# eagle_schematic.net
KiCad netlist of a schematic drawn in EAGLE
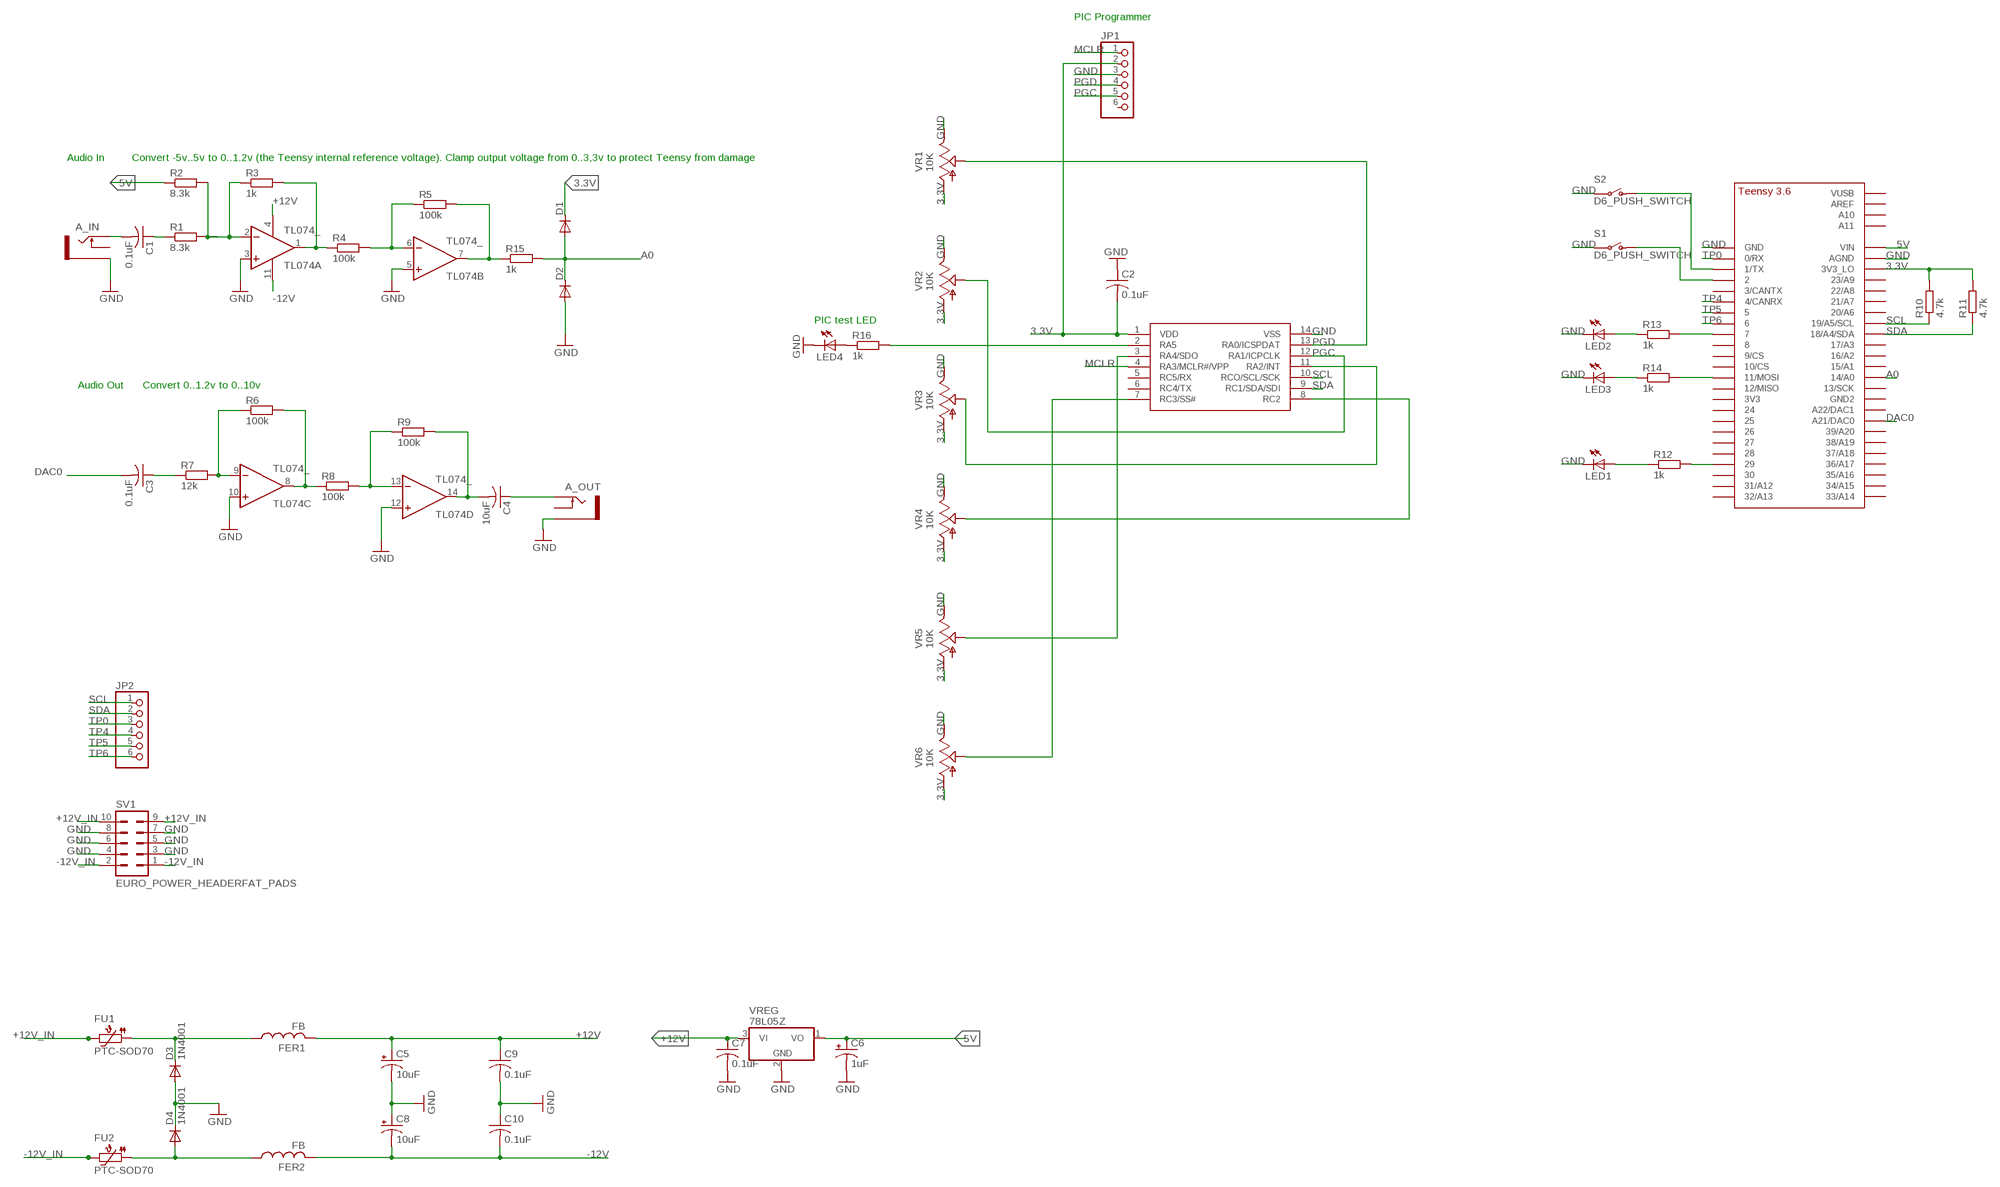
[diagram p0: schematic, sheet 1]

(export (version "E")
  (design (tool "Eeschema 10.0.6"))
  (components
    (comp (ref "A_IN")
      (value "THONKICONNNEW")
      (footprint "eagle-import:WQP-PJ301M-12_JACK")
      (libsource (lib "eagle-import") (part "THONKICONNNEW"))
    )
    (comp (ref "A_OUT")
      (value "THONKICONNNEW")
      (footprint "eagle-import:WQP-PJ301M-12_JACK")
      (libsource (lib "eagle-import") (part "THONKICONNNEW"))
    )
    (comp (ref "C1")
      (value "0.1uF")
      (footprint "eagle-import:C025-030X050")
      (libsource (lib "eagle-import") (part "C-US025-030X050"))
    )
    (comp (ref "C2")
      (value "0.1uF")
      (footprint "eagle-import:C025-030X050")
      (libsource (lib "eagle-import") (part "C-US025-030X050"))
    )
    (comp (ref "C3")
      (value "0.1uF")
      (footprint "eagle-import:C025-030X050")
      (libsource (lib "eagle-import") (part "C-US025-030X050"))
    )
    (comp (ref "C4")
      (value "10uF")
      (footprint "eagle-import:C025-030X050")
      (libsource (lib "eagle-import") (part "C-US025-030X050"))
    )
    (comp (ref "C5")
      (value "10uF")
      (footprint "eagle-import:E2,5-6E")
      (libsource (lib "eagle-import") (part "CPOL-USE2,5-6E"))
    )
    (comp (ref "C6")
      (value "1uF")
      (footprint "eagle-import:E2,5-7")
      (libsource (lib "eagle-import") (part "CPOL-USE2.5-7"))
    )
    (comp (ref "C7")
      (value "0.1uF")
      (footprint "eagle-import:C025-030X050")
      (libsource (lib "eagle-import") (part "C-US025-030X050"))
    )
    (comp (ref "C8")
      (value "10uF")
      (footprint "eagle-import:E2,5-6E")
      (libsource (lib "eagle-import") (part "CPOL-USE2,5-6E"))
    )
    (comp (ref "C9")
      (value "0.1uF")
      (footprint "eagle-import:C025-030X050")
      (libsource (lib "eagle-import") (part "C-US025-030X050"))
    )
    (comp (ref "C10")
      (value "0.1uF")
      (footprint "eagle-import:C025-030X050")
      (libsource (lib "eagle-import") (part "C-US025-030X050"))
    )
    (comp (ref "D1")
      (value "SMALL_DIODEDO35-7")
      (footprint "eagle-import:DO35-7")
      (libsource (lib "eagle-import") (part "SMALL_DIODEDO35-7"))
    )
    (comp (ref "D2")
      (value "SMALL_DIODEDO35-7")
      (footprint "eagle-import:DO35-7")
      (libsource (lib "eagle-import") (part "SMALL_DIODEDO35-7"))
    )
    (comp (ref "D3")
      (value "1N4001")
      (footprint "eagle-import:DO41-10")
      (libsource (lib "eagle-import") (part "1N4004"))
    )
    (comp (ref "D4")
      (value "1N4001")
      (footprint "eagle-import:DO41-10")
      (libsource (lib "eagle-import") (part "1N4004"))
    )
    (comp (ref "FER1")
      (value "FB")
      (footprint "eagle-import:FB")
      (libsource (lib "eagle-import") (part "FB"))
    )
    (comp (ref "FER2")
      (value "FB")
      (footprint "eagle-import:FB")
      (libsource (lib "eagle-import") (part "FB"))
    )
    (comp (ref "FU1")
      (value "PTC-SOD70")
      (footprint "eagle-import:SOD70")
      (libsource (lib "eagle-import") (part "PTC-SOD70"))
    )
    (comp (ref "FU2")
      (value "PTC-SOD70")
      (footprint "eagle-import:SOD70")
      (libsource (lib "eagle-import") (part "PTC-SOD70"))
    )
    (comp (ref "JP1")
      (value "PINHD-1X6")
      (footprint "eagle-import:1X06")
      (libsource (lib "eagle-import") (part "PINHD-1X6"))
    )
    (comp (ref "JP2")
      (value "PINHD-1X6")
      (footprint "eagle-import:1X06")
      (libsource (lib "eagle-import") (part "PINHD-1X6"))
    )
    (comp (ref "LED1")
      (value "LED3MM")
      (footprint "eagle-import:LED3MM")
      (libsource (lib "eagle-import") (part "LED3MM"))
    )
    (comp (ref "LED2")
      (value "LED3MM")
      (footprint "eagle-import:LED3MM")
      (libsource (lib "eagle-import") (part "LED3MM"))
    )
    (comp (ref "LED3")
      (value "LED3MM")
      (footprint "eagle-import:LED3MM")
      (libsource (lib "eagle-import") (part "LED3MM"))
    )
    (comp (ref "LED4")
      (value "LED3MM")
      (footprint "eagle-import:LED3MM")
      (libsource (lib "eagle-import") (part "LED3MM"))
    )
    (comp (ref "PIC")
      (value "PIC16F1825DIL14")
      (footprint "eagle-import:DIL14")
      (libsource (lib "eagle-import") (part "PIC16F1825DIL14"))
    )
    (comp (ref "R1")
      (value "8.3k")
      (footprint "eagle-import:7MM_RESISTOR")
      (libsource (lib "eagle-import") (part "RESISTOR7MM"))
    )
    (comp (ref "R2")
      (value "8.3k")
      (footprint "eagle-import:7MM_RESISTOR")
      (libsource (lib "eagle-import") (part "RESISTOR7MM"))
    )
    (comp (ref "R3")
      (value "1k")
      (footprint "eagle-import:7MM_RESISTOR")
      (libsource (lib "eagle-import") (part "RESISTOR7MM"))
    )
    (comp (ref "R4")
      (value "100k")
      (footprint "eagle-import:7MM_RESISTOR")
      (libsource (lib "eagle-import") (part "RESISTOR7MM"))
    )
    (comp (ref "R5")
      (value "100k")
      (footprint "eagle-import:7MM_RESISTOR")
      (libsource (lib "eagle-import") (part "RESISTOR7MM"))
    )
    (comp (ref "R6")
      (value "100k")
      (footprint "eagle-import:7MM_RESISTOR")
      (libsource (lib "eagle-import") (part "RESISTOR7MM"))
    )
    (comp (ref "R7")
      (value "12k")
      (footprint "eagle-import:7MM_RESISTOR")
      (libsource (lib "eagle-import") (part "RESISTOR7MM"))
    )
    (comp (ref "R8")
      (value "100k")
      (footprint "eagle-import:7MM_RESISTOR")
      (libsource (lib "eagle-import") (part "RESISTOR7MM"))
    )
    (comp (ref "R9")
      (value "100k")
      (footprint "eagle-import:7MM_RESISTOR")
      (libsource (lib "eagle-import") (part "RESISTOR7MM"))
    )
    (comp (ref "R10")
      (value "4.7k")
      (footprint "eagle-import:7MM_RESISTOR")
      (libsource (lib "eagle-import") (part "RESISTOR7MM"))
    )
    (comp (ref "R11")
      (value "4.7k")
      (footprint "eagle-import:7MM_RESISTOR")
      (libsource (lib "eagle-import") (part "RESISTOR7MM"))
    )
    (comp (ref "R12")
      (value "1k")
      (footprint "eagle-import:7MM_RESISTOR")
      (libsource (lib "eagle-import") (part "RESISTOR7MM"))
    )
    (comp (ref "R13")
      (value "1k")
      (footprint "eagle-import:7MM_RESISTOR")
      (libsource (lib "eagle-import") (part "RESISTOR7MM"))
    )
    (comp (ref "R14")
      (value "1k")
      (footprint "eagle-import:7MM_RESISTOR")
      (libsource (lib "eagle-import") (part "RESISTOR7MM"))
    )
    (comp (ref "R15")
      (value "1k")
      (footprint "eagle-import:7MM_RESISTOR")
      (libsource (lib "eagle-import") (part "RESISTOR7MM"))
    )
    (comp (ref "R16")
      (value "1k")
      (footprint "eagle-import:7MM_RESISTOR")
      (libsource (lib "eagle-import") (part "RESISTOR7MM"))
    )
    (comp (ref "S1")
      (value "D6_PUSH_SWITCH")
      (footprint "eagle-import:D6_PUSH_SWITCH")
      (libsource (lib "eagle-import") (part "D6_PUSH_SWITCH"))
    )
    (comp (ref "S2")
      (value "D6_PUSH_SWITCH")
      (footprint "eagle-import:D6_PUSH_SWITCH")
      (libsource (lib "eagle-import") (part "D6_PUSH_SWITCH"))
    )
    (comp (ref "SV1")
      (value "EURO_POWER_HEADERFAT_PADS")
      (footprint "eagle-import:EURO_PWR_HEADER_FAT")
      (libsource (lib "eagle-import") (part "EURO_POWER_HEADERFAT_PADS"))
    )
    (comp (ref "TL074")
      (value "TL074_")
      (footprint "eagle-import:DIL14")
      (libsource (lib "eagle-import") (part "TL074_"))
    )
    (comp (ref "U$1")
      (value "TEENSY_3.5/3.6_BASIC")
      (footprint "eagle-import:TEENSY_3.5_3.6_BASIC")
      (libsource (lib "eagle-import") (part "TEENSY_3.5/3.6_BASIC"))
    )
    (comp (ref "VR1")
      (value "10K")
      (footprint "eagle-import:9MM_SNAP-IN_POT")
      (libsource (lib "eagle-import") (part "9MM_SNAP-IN_POT_"))
    )
    (comp (ref "VR2")
      (value "10K")
      (footprint "eagle-import:9MM_SNAP-IN_POT")
      (libsource (lib "eagle-import") (part "9MM_SNAP-IN_POT_"))
    )
    (comp (ref "VR3")
      (value "10K")
      (footprint "eagle-import:9MM_SNAP-IN_POT")
      (libsource (lib "eagle-import") (part "9MM_SNAP-IN_POT_"))
    )
    (comp (ref "VR4")
      (value "10K")
      (footprint "eagle-import:9MM_SNAP-IN_POT")
      (libsource (lib "eagle-import") (part "9MM_SNAP-IN_POT_"))
    )
    (comp (ref "VR5")
      (value "10K")
      (footprint "eagle-import:9MM_SNAP-IN_POT")
      (libsource (lib "eagle-import") (part "9MM_SNAP-IN_POT_"))
    )
    (comp (ref "VR6")
      (value "10K")
      (footprint "eagle-import:9MM_SNAP-IN_POT")
      (libsource (lib "eagle-import") (part "9MM_SNAP-IN_POT_"))
    )
    (comp (ref "VREG")
      (value "78L05Z")
      (footprint "eagle-import:TO92")
      (libsource (lib "eagle-import") (part "78ZL05"))
    )
  )
  (nets
    (net (code "1") (name "+12V") (class "Default")
      (node (ref "C5") (pin "+") (pinfunction "+_+") (pintype "passive"))
      (node (ref "C7") (pin "1") (pinfunction "1_1") (pintype "passive"))
      (node (ref "C9") (pin "1") (pinfunction "1_1") (pintype "passive"))
      (node (ref "FER1") (pin "P$2") (pinfunction "2_P$2") (pintype "passive"))
      (node (ref "TL074") (pin "4") (pinfunction "V+_4") (pintype "power_in"))
      (node (ref "VREG") (pin "3") (pinfunction "VI_3") (pintype "input"))
    )
    (net (code "2") (name "/+12V_IN") (class "Default")
      (node (ref "FU1") (pin "2") (pinfunction "2_2") (pintype "passive"))
      (node (ref "SV1") (pin "10") (pinfunction "10_10") (pintype "passive"))
      (node (ref "SV1") (pin "9") (pinfunction "9_9") (pintype "passive"))
    )
    (net (code "3") (name "/-12V") (class "Default")
      (node (ref "C10") (pin "2") (pinfunction "2_2") (pintype "passive"))
      (node (ref "C8") (pin "-") (pinfunction "-_-") (pintype "passive"))
      (node (ref "FER2") (pin "P$2") (pinfunction "2_P$2") (pintype "passive"))
      (node (ref "TL074") (pin "11") (pinfunction "V-_11") (pintype "power_in"))
    )
    (net (code "4") (name "/-12V_IN") (class "Default")
      (node (ref "FU2") (pin "2") (pinfunction "2_2") (pintype "passive"))
      (node (ref "SV1") (pin "1") (pinfunction "1_1") (pintype "passive"))
      (node (ref "SV1") (pin "2") (pinfunction "2_2") (pintype "passive"))
    )
    (net (code "5") (name "/A0") (class "Default")
      (node (ref "D1") (pin "A") (pinfunction "A_A") (pintype "passive"))
      (node (ref "D2") (pin "C") (pinfunction "C_C") (pintype "passive"))
      (node (ref "R15") (pin "2") (pinfunction "2_2") (pintype "passive"))
      (node (ref "U$1") (pin "14/A0") (pinfunction "14/A0_14/A0") (pintype "bidirectional"))
    )
    (net (code "6") (name "/DAC0") (class "Default")
      (node (ref "C3") (pin "2") (pinfunction "2_2") (pintype "passive"))
      (node (ref "U$1") (pin "21/DAC0") (pinfunction "A21/DAC0_21/DAC0") (pintype "bidirectional"))
    )
    (net (code "7") (name "/MCLR") (class "Default")
      (node (ref "JP1") (pin "1") (pinfunction "1_1") (pintype "passive"))
      (node (ref "PIC") (pin "4") (pinfunction "RA3/MCLR#/VPP_4") (pintype "input"))
    )
    (net (code "8") (name "/PGC") (class "Default")
      (node (ref "JP1") (pin "5") (pinfunction "5_5") (pintype "passive"))
      (node (ref "PIC") (pin "12") (pinfunction "RA1/ICPCLK_12") (pintype "bidirectional"))
      (node (ref "VR2") (pin "2") (pinfunction "S_2") (pintype "passive"))
    )
    (net (code "9") (name "/PGD") (class "Default")
      (node (ref "JP1") (pin "4") (pinfunction "4_4") (pintype "passive"))
      (node (ref "PIC") (pin "13") (pinfunction "RA0/ICSPDAT_13") (pintype "bidirectional"))
      (node (ref "VR1") (pin "2") (pinfunction "S_2") (pintype "passive"))
    )
    (net (code "10") (name "/SCL") (class "Default")
      (node (ref "JP2") (pin "1") (pinfunction "1_1") (pintype "passive"))
      (node (ref "PIC") (pin "10") (pinfunction "RCO/SCL/SCK_10") (pintype "bidirectional"))
      (node (ref "R10") (pin "1") (pinfunction "1_1") (pintype "passive"))
      (node (ref "U$1") (pin "19/A5/SCL") (pinfunction "19/A5/SCL_19/A5/SCL") (pintype "bidirectional"))
    )
    (net (code "11") (name "/SDA") (class "Default")
      (node (ref "JP2") (pin "2") (pinfunction "2_2") (pintype "passive"))
      (node (ref "PIC") (pin "9") (pinfunction "RC1/SDA/SDI_9") (pintype "bidirectional"))
      (node (ref "R11") (pin "1") (pinfunction "1_1") (pintype "passive"))
      (node (ref "U$1") (pin "18/A4/SDA") (pinfunction "18/A4/SDA_18/A4/SDA") (pintype "bidirectional"))
    )
    (net (code "12") (name "/TP0") (class "Default")
      (node (ref "JP2") (pin "3") (pinfunction "3_3") (pintype "passive"))
      (node (ref "U$1") (pin "0/RX") (pinfunction "0/RX_0/RX") (pintype "bidirectional"))
    )
    (net (code "13") (name "/TP4") (class "Default")
      (node (ref "JP2") (pin "4") (pinfunction "4_4") (pintype "passive"))
      (node (ref "U$1") (pin "4/CANRX") (pinfunction "4/CANRX_4/CANRX") (pintype "bidirectional"))
    )
    (net (code "14") (name "/TP5") (class "Default")
      (node (ref "JP2") (pin "5") (pinfunction "5_5") (pintype "passive"))
      (node (ref "U$1") (pin "5") (pinfunction "5_5") (pintype "bidirectional"))
    )
    (net (code "15") (name "/TP6") (class "Default")
      (node (ref "JP2") (pin "6") (pinfunction "6_6") (pintype "passive"))
      (node (ref "U$1") (pin "6") (pinfunction "6_6") (pintype "bidirectional"))
    )
    (net (code "16") (name "3.3V") (class "Default")
      (node (ref "C2") (pin "2") (pinfunction "2_2") (pintype "passive"))
      (node (ref "D1") (pin "C") (pinfunction "C_C") (pintype "passive"))
      (node (ref "JP1") (pin "2") (pinfunction "2_2") (pintype "passive"))
      (node (ref "PIC") (pin "1") (pinfunction "VDD_1") (pintype "power_in"))
      (node (ref "R10") (pin "2") (pinfunction "2_2") (pintype "passive"))
      (node (ref "R11") (pin "2") (pinfunction "2_2") (pintype "passive"))
      (node (ref "U$1") (pin "3V3_LO") (pinfunction "3V3_LO_3V3_LO") (pintype "bidirectional"))
      (node (ref "VR1") (pin "1") (pinfunction "A_1") (pintype "passive"))
      (node (ref "VR2") (pin "1") (pinfunction "A_1") (pintype "passive"))
      (node (ref "VR3") (pin "1") (pinfunction "A_1") (pintype "passive"))
      (node (ref "VR4") (pin "1") (pinfunction "A_1") (pintype "passive"))
      (node (ref "VR5") (pin "1") (pinfunction "A_1") (pintype "passive"))
      (node (ref "VR6") (pin "1") (pinfunction "A_1") (pintype "passive"))
    )
    (net (code "17") (name "5V") (class "Default")
      (node (ref "C6") (pin "+") (pinfunction "+_+") (pintype "passive"))
      (node (ref "R2") (pin "1") (pinfunction "1_1") (pintype "passive"))
      (node (ref "U$1") (pin "VIN") (pinfunction "VIN_VIN") (pintype "bidirectional"))
      (node (ref "VREG") (pin "1") (pinfunction "VO_1") (pintype "passive"))
    )
    (net (code "18") (name "GND") (class "Default")
      (node (ref "A_IN") (pin "P$3_SLEEVE") (pinfunction "SLEEVE_P$3_SLEEVE") (pintype "passive"))
      (node (ref "A_OUT") (pin "P$3_SLEEVE") (pinfunction "SLEEVE_P$3_SLEEVE") (pintype "passive"))
      (node (ref "C10") (pin "1") (pinfunction "1_1") (pintype "passive"))
      (node (ref "C2") (pin "1") (pinfunction "1_1") (pintype "passive"))
      (node (ref "C5") (pin "-") (pinfunction "-_-") (pintype "passive"))
      (node (ref "C6") (pin "-") (pinfunction "-_-") (pintype "passive"))
      (node (ref "C7") (pin "2") (pinfunction "2_2") (pintype "passive"))
      (node (ref "C8") (pin "+") (pinfunction "+_+") (pintype "passive"))
      (node (ref "C9") (pin "2") (pinfunction "2_2") (pintype "passive"))
      (node (ref "D2") (pin "A") (pinfunction "A_A") (pintype "passive"))
      (node (ref "D3") (pin "A") (pinfunction "A_A") (pintype "passive"))
      (node (ref "D4") (pin "C") (pinfunction "C_C") (pintype "passive"))
      (node (ref "JP1") (pin "3") (pinfunction "3_3") (pintype "passive"))
      (node (ref "LED1") (pin "K") (pinfunction "C_K") (pintype "passive"))
      (node (ref "LED2") (pin "K") (pinfunction "C_K") (pintype "passive"))
      (node (ref "LED3") (pin "K") (pinfunction "C_K") (pintype "passive"))
      (node (ref "LED4") (pin "K") (pinfunction "C_K") (pintype "passive"))
      (node (ref "PIC") (pin "14") (pinfunction "VSS_14") (pintype "power_in"))
      (node (ref "S1") (pin "P$3") (pinfunction "P_P$3") (pintype "passive"))
      (node (ref "S1") (pin "P$4") (pinfunction "P_P$4") (pintype "passive"))
      (node (ref "S2") (pin "P$3") (pinfunction "P_P$3") (pintype "passive"))
      (node (ref "S2") (pin "P$4") (pinfunction "P_P$4") (pintype "passive"))
      (node (ref "SV1") (pin "3") (pinfunction "3_3") (pintype "passive"))
      (node (ref "SV1") (pin "4") (pinfunction "4_4") (pintype "passive"))
      (node (ref "SV1") (pin "5") (pinfunction "5_5") (pintype "passive"))
      (node (ref "SV1") (pin "6") (pinfunction "6_6") (pintype "passive"))
      (node (ref "SV1") (pin "7") (pinfunction "7_7") (pintype "passive"))
      (node (ref "SV1") (pin "8") (pinfunction "8_8") (pintype "passive"))
      (node (ref "TL074") (pin "10") (pinfunction "+IN_10") (pintype "input"))
      (node (ref "TL074") (pin "12") (pinfunction "+IN_12") (pintype "input"))
      (node (ref "TL074") (pin "3") (pinfunction "+IN_3") (pintype "input"))
      (node (ref "TL074") (pin "5") (pinfunction "+IN_5") (pintype "input"))
      (node (ref "U$1") (pin "AGND") (pinfunction "AGND_AGND") (pintype "bidirectional"))
      (node (ref "U$1") (pin "GND") (pinfunction "GND_GND") (pintype "bidirectional"))
      (node (ref "VR1") (pin "3") (pinfunction "E_3") (pintype "passive"))
      (node (ref "VR2") (pin "3") (pinfunction "E_3") (pintype "passive"))
      (node (ref "VR3") (pin "3") (pinfunction "E_3") (pintype "passive"))
      (node (ref "VR4") (pin "3") (pinfunction "E_3") (pintype "passive"))
      (node (ref "VR5") (pin "3") (pinfunction "E_3") (pintype "passive"))
      (node (ref "VR6") (pin "3") (pinfunction "E_3") (pintype "passive"))
      (node (ref "VREG") (pin "2") (pinfunction "GND_2") (pintype "passive"))
    )
    (net (code "19") (name "Net-(A_IN-TIP)") (class "Default")
      (node (ref "A_IN") (pin "P$1_TIP") (pinfunction "TIP_P$1_TIP") (pintype "passive"))
      (node (ref "C1") (pin "2") (pinfunction "2_2") (pintype "passive"))
    )
    (net (code "20") (name "Net-(A_OUT-TIP)") (class "Default")
      (node (ref "A_OUT") (pin "P$1_TIP") (pinfunction "TIP_P$1_TIP") (pintype "passive"))
      (node (ref "C4") (pin "1") (pinfunction "1_1") (pintype "passive"))
    )
    (net (code "21") (name "Net-(C1-Pad1)") (class "Default")
      (node (ref "C1") (pin "1") (pinfunction "1_1") (pintype "passive"))
      (node (ref "R1") (pin "1") (pinfunction "1_1") (pintype "passive"))
    )
    (net (code "22") (name "Net-(C3-Pad1)") (class "Default")
      (node (ref "C3") (pin "1") (pinfunction "1_1") (pintype "passive"))
      (node (ref "R7") (pin "1") (pinfunction "1_1") (pintype "passive"))
    )
    (net (code "23") (name "Net-(FER1-1)") (class "Default")
      (node (ref "D3") (pin "C") (pinfunction "C_C") (pintype "passive"))
      (node (ref "FER1") (pin "P$1") (pinfunction "1_P$1") (pintype "passive"))
      (node (ref "FU1") (pin "1") (pinfunction "1_1") (pintype "passive"))
    )
    (net (code "24") (name "Net-(FER2-1)") (class "Default")
      (node (ref "D4") (pin "A") (pinfunction "A_A") (pintype "passive"))
      (node (ref "FER2") (pin "P$1") (pinfunction "1_P$1") (pintype "passive"))
      (node (ref "FU2") (pin "1") (pinfunction "1_1") (pintype "passive"))
    )
    (net (code "25") (name "Net-(LED1-PadA)") (class "Default")
      (node (ref "LED1") (pin "A") (pinfunction "A_A") (pintype "passive"))
      (node (ref "R12") (pin "1") (pinfunction "1_1") (pintype "passive"))
    )
    (net (code "26") (name "Net-(LED2-PadA)") (class "Default")
      (node (ref "LED2") (pin "A") (pinfunction "A_A") (pintype "passive"))
      (node (ref "R13") (pin "1") (pinfunction "1_1") (pintype "passive"))
    )
    (net (code "27") (name "Net-(LED3-PadA)") (class "Default")
      (node (ref "LED3") (pin "A") (pinfunction "A_A") (pintype "passive"))
      (node (ref "R14") (pin "1") (pinfunction "1_1") (pintype "passive"))
    )
    (net (code "28") (name "Net-(LED4-PadA)") (class "Default")
      (node (ref "LED4") (pin "A") (pinfunction "A_A") (pintype "passive"))
      (node (ref "R16") (pin "1") (pinfunction "1_1") (pintype "passive"))
    )
    (net (code "29") (name "Net-(PIC-RA2{slash}INT)") (class "Default")
      (node (ref "PIC") (pin "11") (pinfunction "RA2/INT_11") (pintype "bidirectional"))
      (node (ref "VR3") (pin "2") (pinfunction "S_2") (pintype "passive"))
    )
    (net (code "30") (name "Net-(PIC-RA4{slash}SDO)") (class "Default")
      (node (ref "PIC") (pin "3") (pinfunction "RA4/SDO_3") (pintype "bidirectional"))
      (node (ref "VR5") (pin "2") (pinfunction "S_2") (pintype "passive"))
    )
    (net (code "31") (name "Net-(PIC-RA5)") (class "Default")
      (node (ref "PIC") (pin "2") (pinfunction "RA5_2") (pintype "bidirectional"))
      (node (ref "R16") (pin "2") (pinfunction "2_2") (pintype "passive"))
    )
    (net (code "32") (name "Net-(PIC-RC2)") (class "Default")
      (node (ref "PIC") (pin "8") (pinfunction "RC2_8") (pintype "bidirectional"))
      (node (ref "VR4") (pin "2") (pinfunction "S_2") (pintype "passive"))
    )
    (net (code "33") (name "Net-(PIC-RC3{slash}SS#)") (class "Default")
      (node (ref "PIC") (pin "7") (pinfunction "RC3/SS#_7") (pintype "bidirectional"))
      (node (ref "VR6") (pin "2") (pinfunction "S_2") (pintype "passive"))
    )
    (net (code "34") (name "Net-(R12-Pad2)") (class "Default")
      (node (ref "R12") (pin "2") (pinfunction "2_2") (pintype "passive"))
      (node (ref "U$1") (pin "29") (pinfunction "29_29") (pintype "bidirectional"))
    )
    (net (code "35") (name "Net-(R13-Pad2)") (class "Default")
      (node (ref "R13") (pin "2") (pinfunction "2_2") (pintype "passive"))
      (node (ref "U$1") (pin "7") (pinfunction "7_7") (pintype "bidirectional"))
    )
    (net (code "36") (name "Net-(R14-Pad2)") (class "Default")
      (node (ref "R14") (pin "2") (pinfunction "2_2") (pintype "passive"))
      (node (ref "U$1") (pin "11/MOSI") (pinfunction "11/MOSI_11/MOSI") (pintype "bidirectional"))
    )
    (net (code "37") (name "Net-(S1-O-PadP$1)") (class "Default")
      (node (ref "S1") (pin "P$1") (pinfunction "O_P$1") (pintype "passive"))
      (node (ref "S1") (pin "P$2") (pinfunction "O_P$2") (pintype "passive"))
      (node (ref "U$1") (pin "2") (pinfunction "2_2") (pintype "bidirectional"))
    )
    (net (code "38") (name "Net-(S2-O-PadP$1)") (class "Default")
      (node (ref "S2") (pin "P$1") (pinfunction "O_P$1") (pintype "passive"))
      (node (ref "S2") (pin "P$2") (pinfunction "O_P$2") (pintype "passive"))
      (node (ref "U$1") (pin "1/TX") (pinfunction "1/TX_1/TX") (pintype "bidirectional"))
    )
    (net (code "39") (name "Net-(TL074A--IN)") (class "Default")
      (node (ref "R1") (pin "2") (pinfunction "2_2") (pintype "passive"))
      (node (ref "R2") (pin "2") (pinfunction "2_2") (pintype "passive"))
      (node (ref "R3") (pin "1") (pinfunction "1_1") (pintype "passive"))
      (node (ref "TL074") (pin "2") (pinfunction "-IN_2") (pintype "input"))
    )
    (net (code "40") (name "Net-(TL074A-OUT)") (class "Default")
      (node (ref "R3") (pin "2") (pinfunction "2_2") (pintype "passive"))
      (node (ref "R4") (pin "1") (pinfunction "1_1") (pintype "passive"))
      (node (ref "TL074") (pin "1") (pinfunction "OUT_1") (pintype "output"))
    )
    (net (code "41") (name "Net-(TL074B--IN)") (class "Default")
      (node (ref "R4") (pin "2") (pinfunction "2_2") (pintype "passive"))
      (node (ref "R5") (pin "1") (pinfunction "1_1") (pintype "passive"))
      (node (ref "TL074") (pin "6") (pinfunction "-IN_6") (pintype "input"))
    )
    (net (code "42") (name "Net-(TL074B-OUT)") (class "Default")
      (node (ref "R15") (pin "1") (pinfunction "1_1") (pintype "passive"))
      (node (ref "R5") (pin "2") (pinfunction "2_2") (pintype "passive"))
      (node (ref "TL074") (pin "7") (pinfunction "OUT_7") (pintype "output"))
    )
    (net (code "43") (name "Net-(TL074C--IN)") (class "Default")
      (node (ref "R6") (pin "1") (pinfunction "1_1") (pintype "passive"))
      (node (ref "R7") (pin "2") (pinfunction "2_2") (pintype "passive"))
      (node (ref "TL074") (pin "9") (pinfunction "-IN_9") (pintype "input"))
    )
    (net (code "44") (name "Net-(TL074C-OUT)") (class "Default")
      (node (ref "R6") (pin "2") (pinfunction "2_2") (pintype "passive"))
      (node (ref "R8") (pin "1") (pinfunction "1_1") (pintype "passive"))
      (node (ref "TL074") (pin "8") (pinfunction "OUT_8") (pintype "output"))
    )
    (net (code "45") (name "Net-(TL074D--IN)") (class "Default")
      (node (ref "R8") (pin "2") (pinfunction "2_2") (pintype "passive"))
      (node (ref "R9") (pin "1") (pinfunction "1_1") (pintype "passive"))
      (node (ref "TL074") (pin "13") (pinfunction "-IN_13") (pintype "input"))
    )
    (net (code "46") (name "Net-(TL074D-OUT)") (class "Default")
      (node (ref "C4") (pin "2") (pinfunction "2_2") (pintype "passive"))
      (node (ref "R9") (pin "2") (pinfunction "2_2") (pintype "passive"))
      (node (ref "TL074") (pin "14") (pinfunction "OUT_14") (pintype "output"))
    )
    (net (code "47") (name "unconnected-(A_IN-SWITCH-PadP$2_SWITCH)") (class "Default")
      (node (ref "A_IN") (pin "P$2_SWITCH") (pinfunction "SWITCH_P$2_SWITCH") (pintype "passive"))
    )
    (net (code "48") (name "unconnected-(A_OUT-SWITCH-PadP$2_SWITCH)") (class "Default")
      (node (ref "A_OUT") (pin "P$2_SWITCH") (pinfunction "SWITCH_P$2_SWITCH") (pintype "passive"))
    )
    (net (code "49") (name "unconnected-(JP1-Pad6)") (class "Default")
      (node (ref "JP1") (pin "6") (pinfunction "6_6") (pintype "passive"))
    )
    (net (code "50") (name "unconnected-(PIC-RC4{slash}TX-Pad6)") (class "Default")
      (node (ref "PIC") (pin "6") (pinfunction "RC4/TX_6") (pintype "bidirectional"))
    )
    (net (code "51") (name "unconnected-(PIC-RC5{slash}RX-Pad5)") (class "Default")
      (node (ref "PIC") (pin "5") (pinfunction "RC5/RX_5") (pintype "bidirectional"))
    )
    (net (code "52") (name "unconnected-(U$1-Pad3V3)") (class "Default")
      (node (ref "U$1") (pin "3V3") (pinfunction "3V3_3V3") (pintype "bidirectional"))
    )
    (net (code "53") (name "unconnected-(U$1-Pad3{slash}CANTX)") (class "Default")
      (node (ref "U$1") (pin "3/CANTX") (pinfunction "3/CANTX_3/CANTX") (pintype "bidirectional"))
    )
    (net (code "54") (name "unconnected-(U$1-Pad8)") (class "Default")
      (node (ref "U$1") (pin "8") (pinfunction "8_8") (pintype "bidirectional"))
    )
    (net (code "55") (name "unconnected-(U$1-Pad9{slash}CS)") (class "Default")
      (node (ref "U$1") (pin "9/CS") (pinfunction "9/CS_9/CS") (pintype "bidirectional"))
    )
    (net (code "56") (name "unconnected-(U$1-Pad10{slash}CS)") (class "Default")
      (node (ref "U$1") (pin "10/CS") (pinfunction "10/CS_10/CS") (pintype "bidirectional"))
    )
    (net (code "57") (name "unconnected-(U$1-Pad12{slash}MISO)") (class "Default")
      (node (ref "U$1") (pin "12/MISO") (pinfunction "12/MISO_12/MISO") (pintype "bidirectional"))
    )
    (net (code "58") (name "unconnected-(U$1-Pad13{slash}SCK)") (class "Default")
      (node (ref "U$1") (pin "13/SCK") (pinfunction "13/SCK_13/SCK") (pintype "bidirectional"))
    )
    (net (code "59") (name "unconnected-(U$1-Pad15{slash}A1)") (class "Default")
      (node (ref "U$1") (pin "15/A1") (pinfunction "15/A1_15/A1") (pintype "bidirectional"))
    )
    (net (code "60") (name "unconnected-(U$1-Pad16{slash}A2)") (class "Default")
      (node (ref "U$1") (pin "16/A2") (pinfunction "16/A2_16/A2") (pintype "bidirectional"))
    )
    (net (code "61") (name "unconnected-(U$1-Pad17{slash}A3)") (class "Default")
      (node (ref "U$1") (pin "17/A3") (pinfunction "17/A3_17/A3") (pintype "bidirectional"))
    )
    (net (code "62") (name "unconnected-(U$1-Pad20{slash}A6)") (class "Default")
      (node (ref "U$1") (pin "20/A6") (pinfunction "20/A6_20/A6") (pintype "bidirectional"))
    )
    (net (code "63") (name "unconnected-(U$1-Pad21{slash}A7)") (class "Default")
      (node (ref "U$1") (pin "21/A7") (pinfunction "21/A7_21/A7") (pintype "bidirectional"))
    )
    (net (code "64") (name "unconnected-(U$1-Pad22{slash}A8)") (class "Default")
      (node (ref "U$1") (pin "22/A8") (pinfunction "22/A8_22/A8") (pintype "bidirectional"))
    )
    (net (code "65") (name "unconnected-(U$1-Pad23{slash}A9)") (class "Default")
      (node (ref "U$1") (pin "23/A9") (pinfunction "23/A9_23/A9") (pintype "bidirectional"))
    )
    (net (code "66") (name "unconnected-(U$1-Pad24)") (class "Default")
      (node (ref "U$1") (pin "24") (pinfunction "24_24") (pintype "bidirectional"))
    )
    (net (code "67") (name "unconnected-(U$1-Pad25)") (class "Default")
      (node (ref "U$1") (pin "25") (pinfunction "25_25") (pintype "bidirectional"))
    )
    (net (code "68") (name "unconnected-(U$1-Pad26)") (class "Default")
      (node (ref "U$1") (pin "26") (pinfunction "26_26") (pintype "bidirectional"))
    )
    (net (code "69") (name "unconnected-(U$1-Pad27)") (class "Default")
      (node (ref "U$1") (pin "27") (pinfunction "27_27") (pintype "bidirectional"))
    )
    (net (code "70") (name "unconnected-(U$1-Pad28)") (class "Default")
      (node (ref "U$1") (pin "28") (pinfunction "28_28") (pintype "bidirectional"))
    )
    (net (code "71") (name "unconnected-(U$1-Pad30)") (class "Default")
      (node (ref "U$1") (pin "30") (pinfunction "30_30") (pintype "bidirectional"))
    )
    (net (code "72") (name "unconnected-(U$1-Pad31{slash}A12)") (class "Default")
      (node (ref "U$1") (pin "31/A12") (pinfunction "31/A12_31/A12") (pintype "bidirectional"))
    )
    (net (code "73") (name "unconnected-(U$1-Pad32{slash}A13)") (class "Default")
      (node (ref "U$1") (pin "32/A13") (pinfunction "32/A13_32/A13") (pintype "bidirectional"))
    )
    (net (code "74") (name "unconnected-(U$1-Pad33{slash}A14)") (class "Default")
      (node (ref "U$1") (pin "33/A14") (pinfunction "33/A14_33/A14") (pintype "bidirectional"))
    )
    (net (code "75") (name "unconnected-(U$1-Pad34{slash}A15)") (class "Default")
      (node (ref "U$1") (pin "34/A15") (pinfunction "34/A15_34/A15") (pintype "bidirectional"))
    )
    (net (code "76") (name "unconnected-(U$1-Pad35{slash}A16)") (class "Default")
      (node (ref "U$1") (pin "35/A16") (pinfunction "35/A16_35/A16") (pintype "bidirectional"))
    )
    (net (code "77") (name "unconnected-(U$1-Pad36{slash}A17)") (class "Default")
      (node (ref "U$1") (pin "36/A17") (pinfunction "36/A17_36/A17") (pintype "bidirectional"))
    )
    (net (code "78") (name "unconnected-(U$1-Pad37{slash}A18)") (class "Default")
      (node (ref "U$1") (pin "37/A18") (pinfunction "37/A18_37/A18") (pintype "bidirectional"))
    )
    (net (code "79") (name "unconnected-(U$1-Pad38{slash}A19)") (class "Default")
      (node (ref "U$1") (pin "38/A19") (pinfunction "38/A19_38/A19") (pintype "bidirectional"))
    )
    (net (code "80") (name "unconnected-(U$1-Pad39{slash}A20)") (class "Default")
      (node (ref "U$1") (pin "39/A20") (pinfunction "39/A20_39/A20") (pintype "bidirectional"))
    )
    (net (code "81") (name "unconnected-(U$1-PadA10)") (class "Default")
      (node (ref "U$1") (pin "A10") (pinfunction "A10_A10") (pintype "bidirectional"))
    )
    (net (code "82") (name "unconnected-(U$1-PadA11)") (class "Default")
      (node (ref "U$1") (pin "A11") (pinfunction "A11_A11") (pintype "bidirectional"))
    )
    (net (code "83") (name "unconnected-(U$1-PadA22{slash}DAC1)") (class "Default")
      (node (ref "U$1") (pin "A22/DAC1") (pinfunction "A22/DAC1_A22/DAC1") (pintype "bidirectional"))
    )
    (net (code "84") (name "unconnected-(U$1-PadAREF)") (class "Default")
      (node (ref "U$1") (pin "AREF") (pinfunction "AREF_AREF") (pintype "bidirectional"))
    )
    (net (code "85") (name "unconnected-(U$1-PadGND2)") (class "Default")
      (node (ref "U$1") (pin "GND2") (pinfunction "GND2_GND2") (pintype "bidirectional"))
    )
    (net (code "86") (name "unconnected-(U$1-PadVUSB)") (class "Default")
      (node (ref "U$1") (pin "VUSB") (pinfunction "VUSB_VUSB") (pintype "bidirectional"))
    )
  )
)
